# OttoPi06a-RPi3AHAT.net
KiCad netlist of a schematic drawn in EAGLE
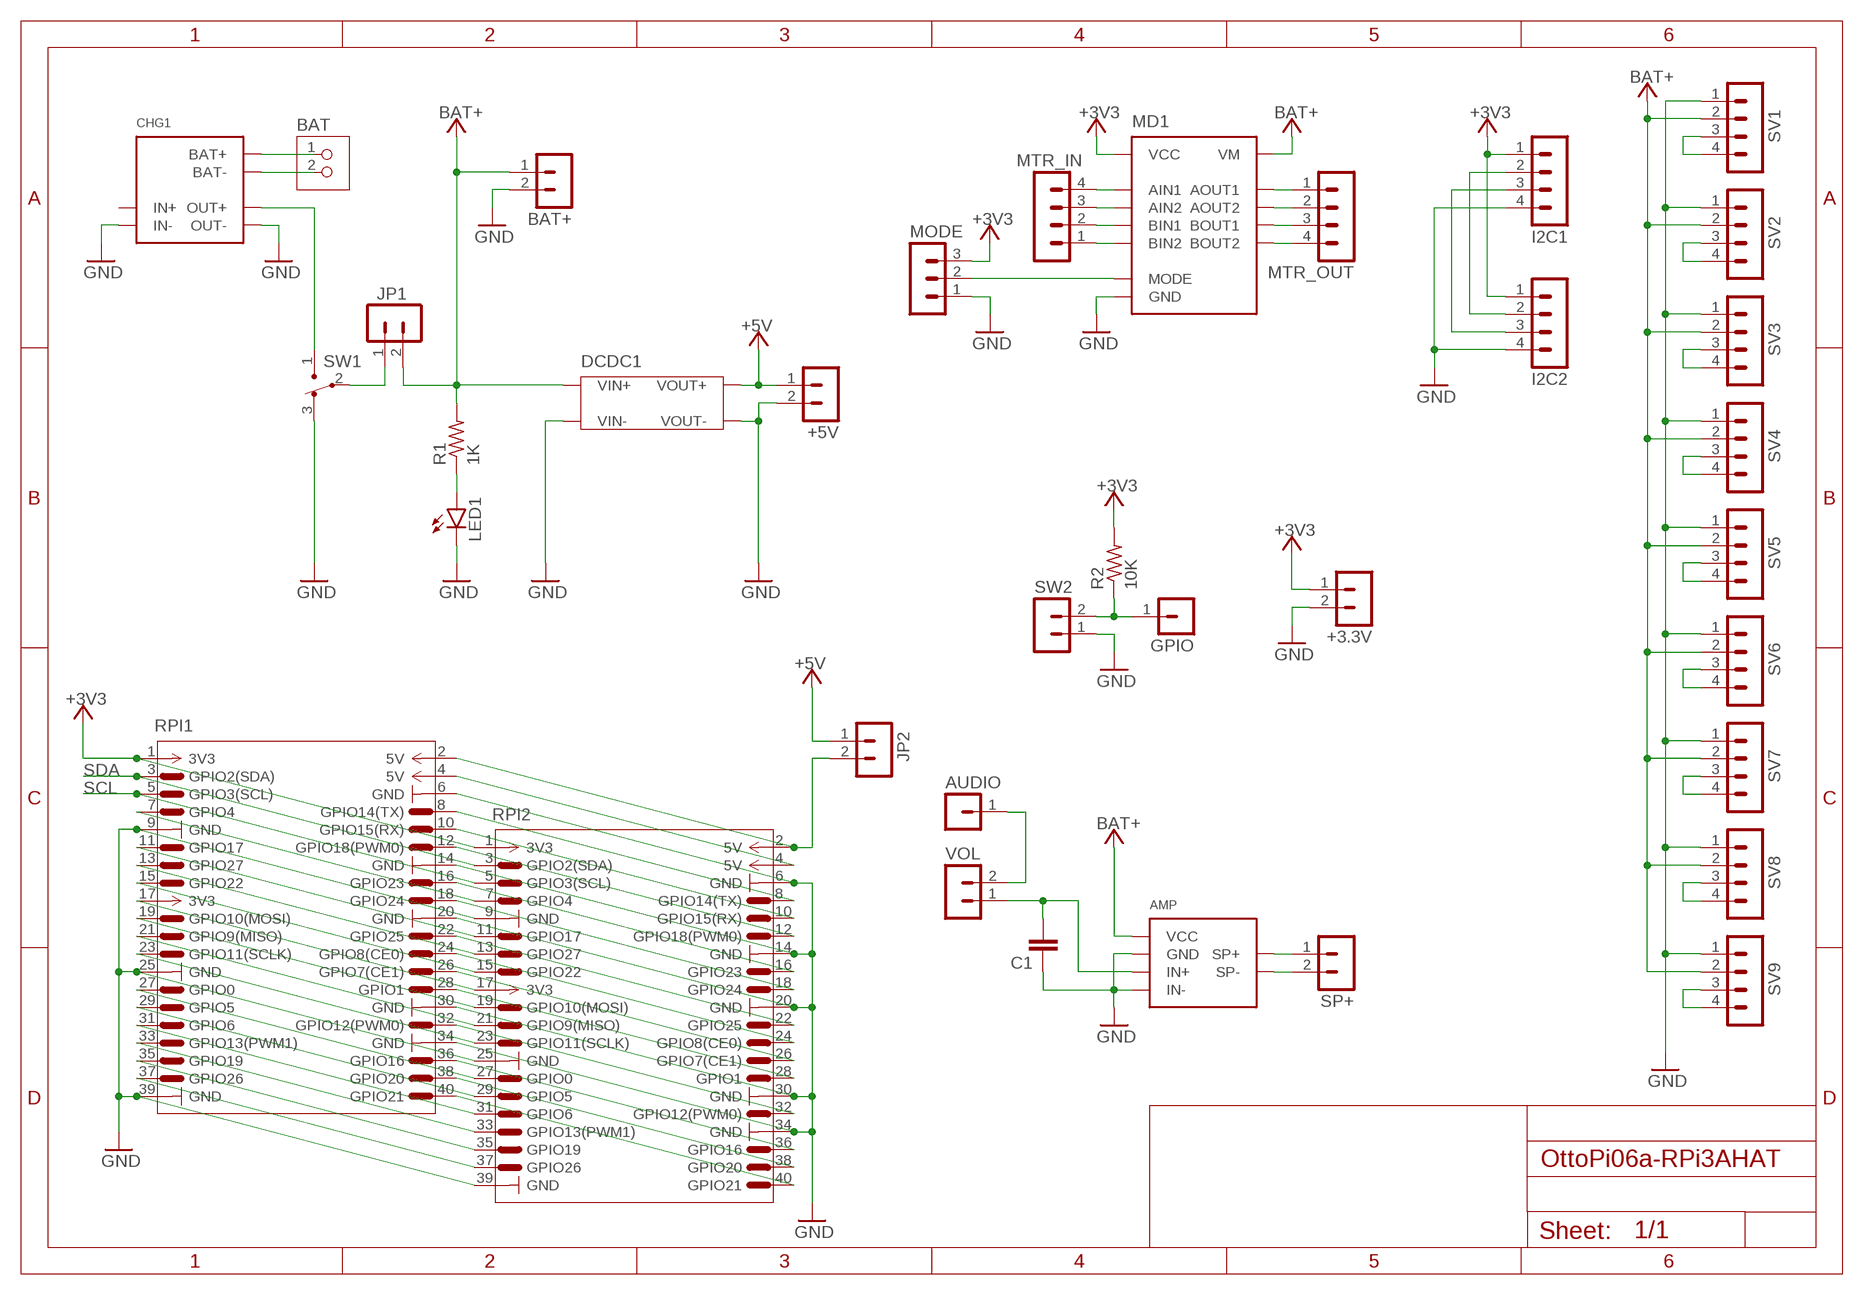
[diagram p0: schematic, sheet 1]

(export (version "E")
  (design (tool "Eeschema 10.0.6"))
  (components
    (comp (ref "+3.3V")
      (value "PINHEAD-MA02-1")
      (footprint "eagle-import:PINHEAD-MA02-1")
      (libsource (lib "eagle-import") (part "PINHEAD-MA02-1"))
    )
    (comp (ref "+5V")
      (value "PINHEAD-MA02-1")
      (footprint "eagle-import:PINHEAD-MA02-1")
      (libsource (lib "eagle-import") (part "PINHEAD-MA02-1"))
    )
    (comp (ref "AMP")
      (value "PAM8012MOD")
      (footprint "eagle-import:PAM8012MOD-A")
      (libsource (lib "eagle-import") (part "PAM8012MOD"))
    )
    (comp (ref "AUDIO")
      (value "PINHEAD-MA01-1")
      (footprint "eagle-import:PINHEAD-MA01-1")
      (libsource (lib "eagle-import") (part "PINHEAD-MA01-1"))
    )
    (comp (ref "BAT")
      (value "JST-PH2")
      (footprint "eagle-import:JST-PH2")
      (libsource (lib "eagle-import") (part "JST-PH2"))
    )
    (comp (ref "BAT+")
      (value "PINHEAD-MA02-1")
      (footprint "eagle-import:PINHEAD-MA02-1")
      (libsource (lib "eagle-import") (part "PINHEAD-MA02-1"))
    )
    (comp (ref "C1")
      (value "C-EU025-024X044")
      (footprint "eagle-import:C025-024X044")
      (libsource (lib "eagle-import") (part "C-EU025-024X044"))
    )
    (comp (ref "CHG1")
      (value "TP4056MOD1")
      (footprint "eagle-import:TP4056MOD1")
      (libsource (lib "eagle-import") (part "TP4056MOD1"))
    )
    (comp (ref "DCDC1")
      (value "DCDC-MT3608-MODUSB")
      (footprint "eagle-import:DCDC-MT3608-MOD2-USB")
      (libsource (lib "eagle-import") (part "DCDC-MT3608-MODUSB"))
    )
    (comp (ref "GPIO")
      (value "PINHEAD-MA01-1")
      (footprint "eagle-import:PINHEAD-MA01-1")
      (libsource (lib "eagle-import") (part "PINHEAD-MA01-1"))
    )
    (comp (ref "I2C1")
      (value "PINHEAD-MA04-1")
      (footprint "eagle-import:PINHEAD-MA04-1")
      (libsource (lib "eagle-import") (part "PINHEAD-MA04-1"))
    )
    (comp (ref "I2C2")
      (value "PINHEAD-MA04-1")
      (footprint "eagle-import:PINHEAD-MA04-1")
      (libsource (lib "eagle-import") (part "PINHEAD-MA04-1"))
    )
    (comp (ref "JP1")
      (value "PINHEAD-MA02-1")
      (footprint "eagle-import:PINHEAD-MA02-1")
      (libsource (lib "eagle-import") (part "PINHEAD-MA02-1"))
    )
    (comp (ref "JP2")
      (value "PINHEAD-MA02-1")
      (footprint "eagle-import:PINHEAD-MA02-1")
      (libsource (lib "eagle-import") (part "PINHEAD-MA02-1"))
    )
    (comp (ref "LED1")
      (value "LED3MM")
      (footprint "eagle-import:LED3MM")
      (libsource (lib "eagle-import") (part "LED3MM"))
    )
    (comp (ref "MD1")
      (value "DRV8835MOD")
      (footprint "eagle-import:DRV8835MOD")
      (libsource (lib "eagle-import") (part "DRV8835MOD"))
    )
    (comp (ref "MODE")
      (value "PINHEAD-MA03-1")
      (footprint "eagle-import:PINHEAD-MA03-1")
      (libsource (lib "eagle-import") (part "PINHEAD-MA03-1"))
    )
    (comp (ref "MTR_IN")
      (value "PINHEAD-MA04-1")
      (footprint "eagle-import:PINHEAD-MA04-1")
      (libsource (lib "eagle-import") (part "PINHEAD-MA04-1"))
    )
    (comp (ref "MTR_OUT")
      (value "PINHEAD-MA04-1")
      (footprint "eagle-import:PINHEAD-MA04-1")
      (libsource (lib "eagle-import") (part "PINHEAD-MA04-1"))
    )
    (comp (ref "R1")
      (value "1K")
      (footprint "eagle-import:0204_7")
      (libsource (lib "eagle-import") (part "R-US_0204/7"))
    )
    (comp (ref "R2")
      (value "10K")
      (footprint "eagle-import:0204_7")
      (libsource (lib "eagle-import") (part "R-US_0204/7"))
    )
    (comp (ref "RPI1")
      (value "RPI-PIN")
      (footprint "eagle-import:RPI-PIN")
      (libsource (lib "eagle-import") (part "RPI-PIN"))
    )
    (comp (ref "RPI2")
      (value "RPI-PIN")
      (footprint "eagle-import:RPI-PIN")
      (libsource (lib "eagle-import") (part "RPI-PIN"))
    )
    (comp (ref "SP+")
      (value "PINHEAD-MA02-1")
      (footprint "eagle-import:PINHEAD-MA02-1")
      (libsource (lib "eagle-import") (part "PINHEAD-MA02-1"))
    )
    (comp (ref "SV1")
      (value "PINHEAD-MA04-1")
      (footprint "eagle-import:PINHEAD-MA04-1")
      (libsource (lib "eagle-import") (part "PINHEAD-MA04-1"))
    )
    (comp (ref "SV2")
      (value "PINHEAD-MA04-1")
      (footprint "eagle-import:PINHEAD-MA04-1")
      (libsource (lib "eagle-import") (part "PINHEAD-MA04-1"))
    )
    (comp (ref "SV3")
      (value "PINHEAD-MA04-1")
      (footprint "eagle-import:PINHEAD-MA04-1")
      (libsource (lib "eagle-import") (part "PINHEAD-MA04-1"))
    )
    (comp (ref "SV4")
      (value "PINHEAD-MA04-1")
      (footprint "eagle-import:PINHEAD-MA04-1")
      (libsource (lib "eagle-import") (part "PINHEAD-MA04-1"))
    )
    (comp (ref "SV5")
      (value "PINHEAD-MA04-1")
      (footprint "eagle-import:PINHEAD-MA04-1")
      (libsource (lib "eagle-import") (part "PINHEAD-MA04-1"))
    )
    (comp (ref "SV6")
      (value "PINHEAD-MA04-1")
      (footprint "eagle-import:PINHEAD-MA04-1")
      (libsource (lib "eagle-import") (part "PINHEAD-MA04-1"))
    )
    (comp (ref "SV7")
      (value "PINHEAD-MA04-1")
      (footprint "eagle-import:PINHEAD-MA04-1")
      (libsource (lib "eagle-import") (part "PINHEAD-MA04-1"))
    )
    (comp (ref "SV8")
      (value "PINHEAD-MA04-1")
      (footprint "eagle-import:PINHEAD-MA04-1")
      (libsource (lib "eagle-import") (part "PINHEAD-MA04-1"))
    )
    (comp (ref "SV9")
      (value "PINHEAD-MA04-1")
      (footprint "eagle-import:PINHEAD-MA04-1")
      (libsource (lib "eagle-import") (part "PINHEAD-MA04-1"))
    )
    (comp (ref "SW1")
      (value "SW3-1")
      (footprint "eagle-import:SW3-1")
      (fields (field (name "MF") "HiLetgo"))
      (libsource (lib "eagle-import") (part "SW3-1"))
    )
    (comp (ref "SW2")
      (value "PINHEAD-MA02-1")
      (footprint "eagle-import:PINHEAD-MA02-1")
      (libsource (lib "eagle-import") (part "PINHEAD-MA02-1"))
    )
    (comp (ref "VOL")
      (value "PINHEAD-MA02-1")
      (footprint "eagle-import:PINHEAD-MA02-1")
      (libsource (lib "eagle-import") (part "PINHEAD-MA02-1"))
    )
  )
  (nets
    (net (code "1") (name "+3V3") (class "Default")
      (node (ref "+3.3V") (pin "1") (pinfunction "1_1") (pintype "passive"))
      (node (ref "I2C1") (pin "1") (pinfunction "1_1") (pintype "passive"))
      (node (ref "I2C2") (pin "1") (pinfunction "1_1") (pintype "passive"))
      (node (ref "MD1") (pin "VCC") (pinfunction "VCC_VCC") (pintype "input"))
      (node (ref "MODE") (pin "3") (pinfunction "3_3") (pintype "passive"))
      (node (ref "R2") (pin "2") (pinfunction "2_2") (pintype "passive"))
      (node (ref "RPI1") (pin "1") (pinfunction "3V3_1") (pintype "passive"))
      (node (ref "RPI2") (pin "1") (pinfunction "3V3_1") (pintype "passive"))
    )
    (net (code "2") (name "+5V") (class "Default")
      (node (ref "+5V") (pin "1") (pinfunction "1_1") (pintype "passive"))
      (node (ref "DCDC1") (pin "VOUT+") (pinfunction "VOUT+_VOUT+") (pintype "power_in"))
      (node (ref "JP2") (pin "1") (pinfunction "1_1") (pintype "passive"))
    )
    (net (code "3") (name "/SCL") (class "Default")
      (node (ref "I2C1") (pin "3") (pinfunction "3_3") (pintype "passive"))
      (node (ref "I2C2") (pin "3") (pinfunction "3_3") (pintype "passive"))
      (node (ref "RPI1") (pin "5") (pinfunction "GPIO3(SCL)_5") (pintype "passive"))
      (node (ref "RPI2") (pin "5") (pinfunction "GPIO3(SCL)_5") (pintype "passive"))
    )
    (net (code "4") (name "/SDA") (class "Default")
      (node (ref "I2C1") (pin "2") (pinfunction "2_2") (pintype "passive"))
      (node (ref "I2C2") (pin "2") (pinfunction "2_2") (pintype "passive"))
      (node (ref "RPI1") (pin "3") (pinfunction "GPIO2(SDA)_3") (pintype "passive"))
      (node (ref "RPI2") (pin "3") (pinfunction "GPIO2(SDA)_3") (pintype "passive"))
    )
    (net (code "5") (name "BAT+") (class "Default")
      (node (ref "AMP") (pin "V+") (pinfunction "VCC_V+") (pintype "passive"))
      (node (ref "BAT+") (pin "1") (pinfunction "1_1") (pintype "passive"))
      (node (ref "DCDC1") (pin "VIN+") (pinfunction "VIN+_VIN+") (pintype "power_in"))
      (node (ref "JP1") (pin "2") (pinfunction "2_2") (pintype "passive"))
      (node (ref "MD1") (pin "VM") (pinfunction "VM_VM") (pintype "input"))
      (node (ref "R1") (pin "2") (pinfunction "2_2") (pintype "passive"))
      (node (ref "SV1") (pin "2") (pinfunction "2_2") (pintype "passive"))
      (node (ref "SV2") (pin "2") (pinfunction "2_2") (pintype "passive"))
      (node (ref "SV3") (pin "2") (pinfunction "2_2") (pintype "passive"))
      (node (ref "SV4") (pin "2") (pinfunction "2_2") (pintype "passive"))
      (node (ref "SV5") (pin "2") (pinfunction "2_2") (pintype "passive"))
      (node (ref "SV6") (pin "2") (pinfunction "2_2") (pintype "passive"))
      (node (ref "SV7") (pin "2") (pinfunction "2_2") (pintype "passive"))
      (node (ref "SV8") (pin "2") (pinfunction "2_2") (pintype "passive"))
      (node (ref "SV9") (pin "2") (pinfunction "2_2") (pintype "passive"))
    )
    (net (code "6") (name "GND") (class "Default")
      (node (ref "+3.3V") (pin "2") (pinfunction "2_2") (pintype "passive"))
      (node (ref "+5V") (pin "2") (pinfunction "2_2") (pintype "passive"))
      (node (ref "AMP") (pin "GND") (pinfunction "GND_GND") (pintype "passive"))
      (node (ref "AMP") (pin "IN-") (pinfunction "IN-_IN-") (pintype "input"))
      (node (ref "BAT+") (pin "2") (pinfunction "2_2") (pintype "passive"))
      (node (ref "C1") (pin "1") (pinfunction "1_1") (pintype "passive"))
      (node (ref "CHG1") (pin "IN-") (pinfunction "IN-_IN-") (pintype "passive"))
      (node (ref "CHG1") (pin "OUT-") (pinfunction "OUT-_OUT-") (pintype "passive"))
      (node (ref "DCDC1") (pin "VIN-") (pinfunction "VIN-_VIN-") (pintype "power_in"))
      (node (ref "DCDC1") (pin "VOUT-") (pinfunction "VOUT-_VOUT-") (pintype "power_in"))
      (node (ref "I2C1") (pin "4") (pinfunction "4_4") (pintype "passive"))
      (node (ref "I2C2") (pin "4") (pinfunction "4_4") (pintype "passive"))
      (node (ref "LED1") (pin "K") (pinfunction "C_K") (pintype "passive"))
      (node (ref "MD1") (pin "GND") (pinfunction "GND_GND") (pintype "power_in"))
      (node (ref "MODE") (pin "1") (pinfunction "1_1") (pintype "passive"))
      (node (ref "RPI1") (pin "14") (pinfunction "GND_14") (pintype "passive"))
      (node (ref "RPI1") (pin "20") (pinfunction "GND_20") (pintype "passive"))
      (node (ref "RPI1") (pin "25") (pinfunction "GND_25") (pintype "passive"))
      (node (ref "RPI1") (pin "30") (pinfunction "GND_30") (pintype "passive"))
      (node (ref "RPI1") (pin "34") (pinfunction "GND_34") (pintype "passive"))
      (node (ref "RPI1") (pin "39") (pinfunction "GND_39") (pintype "passive"))
      (node (ref "RPI1") (pin "6") (pinfunction "GND_6") (pintype "passive"))
      (node (ref "RPI1") (pin "9") (pinfunction "GND_9") (pintype "passive"))
      (node (ref "RPI2") (pin "14") (pinfunction "GND_14") (pintype "passive"))
      (node (ref "RPI2") (pin "20") (pinfunction "GND_20") (pintype "passive"))
      (node (ref "RPI2") (pin "25") (pinfunction "GND_25") (pintype "passive"))
      (node (ref "RPI2") (pin "30") (pinfunction "GND_30") (pintype "passive"))
      (node (ref "RPI2") (pin "34") (pinfunction "GND_34") (pintype "passive"))
      (node (ref "RPI2") (pin "39") (pinfunction "GND_39") (pintype "passive"))
      (node (ref "RPI2") (pin "6") (pinfunction "GND_6") (pintype "passive"))
      (node (ref "RPI2") (pin "9") (pinfunction "GND_9") (pintype "passive"))
      (node (ref "SV1") (pin "1") (pinfunction "1_1") (pintype "passive"))
      (node (ref "SV2") (pin "1") (pinfunction "1_1") (pintype "passive"))
      (node (ref "SV3") (pin "1") (pinfunction "1_1") (pintype "passive"))
      (node (ref "SV4") (pin "1") (pinfunction "1_1") (pintype "passive"))
      (node (ref "SV5") (pin "1") (pinfunction "1_1") (pintype "passive"))
      (node (ref "SV6") (pin "1") (pinfunction "1_1") (pintype "passive"))
      (node (ref "SV7") (pin "1") (pinfunction "1_1") (pintype "passive"))
      (node (ref "SV8") (pin "1") (pinfunction "1_1") (pintype "passive"))
      (node (ref "SV9") (pin "1") (pinfunction "1_1") (pintype "passive"))
      (node (ref "SW1") (pin "3") (pinfunction "3_3") (pintype "passive"))
      (node (ref "SW2") (pin "1") (pinfunction "1_1") (pintype "passive"))
    )
    (net (code "7") (name "Net-(AMP-PadIN+)") (class "Default")
      (node (ref "AMP") (pin "IN+") (pinfunction "IN+_IN+") (pintype "input"))
      (node (ref "C1") (pin "2") (pinfunction "2_2") (pintype "passive"))
      (node (ref "VOL") (pin "1") (pinfunction "1_1") (pintype "passive"))
    )
    (net (code "8") (name "Net-(AMP-SP+)") (class "Default")
      (node (ref "AMP") (pin "SP+@1") (pinfunction "SP+_SP+@1") (pintype "output"))
      (node (ref "SP+") (pin "1") (pinfunction "1_1") (pintype "passive"))
    )
    (net (code "9") (name "Net-(AMP-SP-)") (class "Default")
      (node (ref "AMP") (pin "SP-@1") (pinfunction "SP-_SP-@1") (pintype "output"))
      (node (ref "SP+") (pin "2") (pinfunction "2_2") (pintype "passive"))
    )
    (net (code "10") (name "Net-(AUDIO-Pad1)") (class "Default")
      (node (ref "AUDIO") (pin "1") (pinfunction "1_1") (pintype "passive"))
      (node (ref "VOL") (pin "2") (pinfunction "2_2") (pintype "passive"))
    )
    (net (code "11") (name "Net-(BAT-Pad1)") (class "Default")
      (node (ref "BAT") (pin "1") (pinfunction "1_1") (pintype "passive"))
      (node (ref "CHG1") (pin "BAT+") (pinfunction "BAT+_BAT+") (pintype "passive"))
    )
    (net (code "12") (name "Net-(BAT-Pad2)") (class "Default")
      (node (ref "BAT") (pin "2") (pinfunction "2_2") (pintype "passive"))
      (node (ref "CHG1") (pin "BAT-") (pinfunction "BAT-_BAT-") (pintype "passive"))
    )
    (net (code "13") (name "Net-(CHG1-PadOUT+)") (class "Default")
      (node (ref "CHG1") (pin "OUT+") (pinfunction "OUT+_OUT+") (pintype "passive"))
      (node (ref "SW1") (pin "1") (pinfunction "1_1") (pintype "passive"))
    )
    (net (code "14") (name "Net-(GPIO-Pad1)") (class "Default")
      (node (ref "GPIO") (pin "1") (pinfunction "1_1") (pintype "passive"))
      (node (ref "R2") (pin "1") (pinfunction "1_1") (pintype "passive"))
      (node (ref "SW2") (pin "2") (pinfunction "2_2") (pintype "passive"))
    )
    (net (code "15") (name "Net-(JP1-Pad1)") (class "Default")
      (node (ref "JP1") (pin "1") (pinfunction "1_1") (pintype "passive"))
      (node (ref "SW1") (pin "2") (pinfunction "2_2") (pintype "passive"))
    )
    (net (code "16") (name "Net-(JP2-Pad2)") (class "Default")
      (node (ref "JP2") (pin "2") (pinfunction "2_2") (pintype "passive"))
      (node (ref "RPI1") (pin "2") (pinfunction "5V_2") (pintype "passive"))
      (node (ref "RPI2") (pin "2") (pinfunction "5V_2") (pintype "passive"))
    )
    (net (code "17") (name "Net-(LED1-PadA)") (class "Default")
      (node (ref "LED1") (pin "A") (pinfunction "A_A") (pintype "passive"))
      (node (ref "R1") (pin "1") (pinfunction "1_1") (pintype "passive"))
    )
    (net (code "18") (name "Net-(MD1-PadAIN1)") (class "Default")
      (node (ref "MD1") (pin "AIN1") (pinfunction "AIN1_AIN1") (pintype "input"))
      (node (ref "MTR_IN") (pin "4") (pinfunction "4_4") (pintype "passive"))
    )
    (net (code "19") (name "Net-(MD1-PadAIN2)") (class "Default")
      (node (ref "MD1") (pin "AIN2") (pinfunction "AIN2_AIN2") (pintype "input"))
      (node (ref "MTR_IN") (pin "3") (pinfunction "3_3") (pintype "passive"))
    )
    (net (code "20") (name "Net-(MD1-PadAOUT1)") (class "Default")
      (node (ref "MD1") (pin "AOUT1") (pinfunction "AOUT1_AOUT1") (pintype "output"))
      (node (ref "MTR_OUT") (pin "1") (pinfunction "1_1") (pintype "passive"))
    )
    (net (code "21") (name "Net-(MD1-PadAOUT2)") (class "Default")
      (node (ref "MD1") (pin "AOUT2") (pinfunction "AOUT2_AOUT2") (pintype "output"))
      (node (ref "MTR_OUT") (pin "2") (pinfunction "2_2") (pintype "passive"))
    )
    (net (code "22") (name "Net-(MD1-PadBIN1)") (class "Default")
      (node (ref "MD1") (pin "BIN1") (pinfunction "BIN1_BIN1") (pintype "input"))
      (node (ref "MTR_IN") (pin "2") (pinfunction "2_2") (pintype "passive"))
    )
    (net (code "23") (name "Net-(MD1-PadBIN2)") (class "Default")
      (node (ref "MD1") (pin "BIN2") (pinfunction "BIN2_BIN2") (pintype "input"))
      (node (ref "MTR_IN") (pin "1") (pinfunction "1_1") (pintype "passive"))
    )
    (net (code "24") (name "Net-(MD1-PadBOUT1)") (class "Default")
      (node (ref "MD1") (pin "BOUT1") (pinfunction "BOUT1_BOUT1") (pintype "output"))
      (node (ref "MTR_OUT") (pin "3") (pinfunction "3_3") (pintype "passive"))
    )
    (net (code "25") (name "Net-(MD1-PadBOUT2)") (class "Default")
      (node (ref "MD1") (pin "BOUT2") (pinfunction "BOUT2_BOUT2") (pintype "output"))
      (node (ref "MTR_OUT") (pin "4") (pinfunction "4_4") (pintype "passive"))
    )
    (net (code "26") (name "Net-(MD1-PadMODE)") (class "Default")
      (node (ref "MD1") (pin "MODE") (pinfunction "MODE_MODE") (pintype "input"))
      (node (ref "MODE") (pin "2") (pinfunction "2_2") (pintype "passive"))
    )
    (net (code "27") (name "Net-(RPI1-3V3-Pad17)") (class "Default")
      (node (ref "RPI1") (pin "17") (pinfunction "3V3_17") (pintype "passive"))
      (node (ref "RPI2") (pin "17") (pinfunction "3V3_17") (pintype "passive"))
    )
    (net (code "28") (name "Net-(RPI1-5V-Pad4)") (class "Default")
      (node (ref "RPI1") (pin "4") (pinfunction "5V_4") (pintype "passive"))
      (node (ref "RPI2") (pin "4") (pinfunction "5V_4") (pintype "passive"))
    )
    (net (code "29") (name "Net-(RPI1-GPIO0)") (class "Default")
      (node (ref "RPI1") (pin "27") (pinfunction "GPIO0_27") (pintype "passive"))
      (node (ref "RPI2") (pin "27") (pinfunction "GPIO0_27") (pintype "passive"))
    )
    (net (code "30") (name "Net-(RPI1-GPIO1)") (class "Default")
      (node (ref "RPI1") (pin "28") (pinfunction "GPIO1_28") (pintype "passive"))
      (node (ref "RPI2") (pin "28") (pinfunction "GPIO1_28") (pintype "passive"))
    )
    (net (code "31") (name "Net-(RPI1-GPIO4)") (class "Default")
      (node (ref "RPI1") (pin "7") (pinfunction "GPIO4_7") (pintype "passive"))
      (node (ref "RPI2") (pin "7") (pinfunction "GPIO4_7") (pintype "passive"))
    )
    (net (code "32") (name "Net-(RPI1-GPIO5)") (class "Default")
      (node (ref "RPI1") (pin "29") (pinfunction "GPIO5_29") (pintype "passive"))
      (node (ref "RPI2") (pin "29") (pinfunction "GPIO5_29") (pintype "passive"))
    )
    (net (code "33") (name "Net-(RPI1-GPIO6)") (class "Default")
      (node (ref "RPI1") (pin "31") (pinfunction "GPIO6_31") (pintype "passive"))
      (node (ref "RPI2") (pin "31") (pinfunction "GPIO6_31") (pintype "passive"))
    )
    (net (code "34") (name "Net-(RPI1-GPIO7(CE1))") (class "Default")
      (node (ref "RPI1") (pin "26") (pinfunction "GPIO7(CE1)_26") (pintype "passive"))
      (node (ref "RPI2") (pin "26") (pinfunction "GPIO7(CE1)_26") (pintype "passive"))
    )
    (net (code "35") (name "Net-(RPI1-GPIO8(CE0))") (class "Default")
      (node (ref "RPI1") (pin "24") (pinfunction "GPIO8(CE0)_24") (pintype "passive"))
      (node (ref "RPI2") (pin "24") (pinfunction "GPIO8(CE0)_24") (pintype "passive"))
    )
    (net (code "36") (name "Net-(RPI1-GPIO9(MISO))") (class "Default")
      (node (ref "RPI1") (pin "21") (pinfunction "GPIO9(MISO)_21") (pintype "passive"))
      (node (ref "RPI2") (pin "21") (pinfunction "GPIO9(MISO)_21") (pintype "passive"))
    )
    (net (code "37") (name "Net-(RPI1-GPIO10(MOSI))") (class "Default")
      (node (ref "RPI1") (pin "19") (pinfunction "GPIO10(MOSI)_19") (pintype "passive"))
      (node (ref "RPI2") (pin "19") (pinfunction "GPIO10(MOSI)_19") (pintype "passive"))
    )
    (net (code "38") (name "Net-(RPI1-GPIO11(SCLK))") (class "Default")
      (node (ref "RPI1") (pin "23") (pinfunction "GPIO11(SCLK)_23") (pintype "passive"))
      (node (ref "RPI2") (pin "23") (pinfunction "GPIO11(SCLK)_23") (pintype "passive"))
    )
    (net (code "39") (name "Net-(RPI1-GPIO12(PWM0))") (class "Default")
      (node (ref "RPI1") (pin "32") (pinfunction "GPIO12(PWM0)_32") (pintype "passive"))
      (node (ref "RPI2") (pin "32") (pinfunction "GPIO12(PWM0)_32") (pintype "passive"))
    )
    (net (code "40") (name "Net-(RPI1-GPIO13(PWM1))") (class "Default")
      (node (ref "RPI1") (pin "33") (pinfunction "GPIO13(PWM1)_33") (pintype "passive"))
      (node (ref "RPI2") (pin "33") (pinfunction "GPIO13(PWM1)_33") (pintype "passive"))
    )
    (net (code "41") (name "Net-(RPI1-GPIO14(TX))") (class "Default")
      (node (ref "RPI1") (pin "8") (pinfunction "GPIO14(TX)_8") (pintype "passive"))
      (node (ref "RPI2") (pin "8") (pinfunction "GPIO14(TX)_8") (pintype "passive"))
    )
    (net (code "42") (name "Net-(RPI1-GPIO15(RX))") (class "Default")
      (node (ref "RPI1") (pin "10") (pinfunction "GPIO15(RX)_10") (pintype "passive"))
      (node (ref "RPI2") (pin "10") (pinfunction "GPIO15(RX)_10") (pintype "passive"))
    )
    (net (code "43") (name "Net-(RPI1-GPIO16)") (class "Default")
      (node (ref "RPI1") (pin "36") (pinfunction "GPIO16_36") (pintype "passive"))
      (node (ref "RPI2") (pin "36") (pinfunction "GPIO16_36") (pintype "passive"))
    )
    (net (code "44") (name "Net-(RPI1-GPIO17)") (class "Default")
      (node (ref "RPI1") (pin "11") (pinfunction "GPIO17_11") (pintype "passive"))
      (node (ref "RPI2") (pin "11") (pinfunction "GPIO17_11") (pintype "passive"))
    )
    (net (code "45") (name "Net-(RPI1-GPIO18(PWM0))") (class "Default")
      (node (ref "RPI1") (pin "12") (pinfunction "GPIO18(PWM0)_12") (pintype "passive"))
      (node (ref "RPI2") (pin "12") (pinfunction "GPIO18(PWM0)_12") (pintype "passive"))
    )
    (net (code "46") (name "Net-(RPI1-GPIO19)") (class "Default")
      (node (ref "RPI1") (pin "35") (pinfunction "GPIO19_35") (pintype "passive"))
      (node (ref "RPI2") (pin "35") (pinfunction "GPIO19_35") (pintype "passive"))
    )
    (net (code "47") (name "Net-(RPI1-GPIO20)") (class "Default")
      (node (ref "RPI1") (pin "38") (pinfunction "GPIO20_38") (pintype "passive"))
      (node (ref "RPI2") (pin "38") (pinfunction "GPIO20_38") (pintype "passive"))
    )
    (net (code "48") (name "Net-(RPI1-GPIO21)") (class "Default")
      (node (ref "RPI1") (pin "40") (pinfunction "GPIO21_40") (pintype "passive"))
      (node (ref "RPI2") (pin "40") (pinfunction "GPIO21_40") (pintype "passive"))
    )
    (net (code "49") (name "Net-(RPI1-GPIO22)") (class "Default")
      (node (ref "RPI1") (pin "15") (pinfunction "GPIO22_15") (pintype "passive"))
      (node (ref "RPI2") (pin "15") (pinfunction "GPIO22_15") (pintype "passive"))
    )
    (net (code "50") (name "Net-(RPI1-GPIO23)") (class "Default")
      (node (ref "RPI1") (pin "16") (pinfunction "GPIO23_16") (pintype "passive"))
      (node (ref "RPI2") (pin "16") (pinfunction "GPIO23_16") (pintype "passive"))
    )
    (net (code "51") (name "Net-(RPI1-GPIO24)") (class "Default")
      (node (ref "RPI1") (pin "18") (pinfunction "GPIO24_18") (pintype "passive"))
      (node (ref "RPI2") (pin "18") (pinfunction "GPIO24_18") (pintype "passive"))
    )
    (net (code "52") (name "Net-(RPI1-GPIO25)") (class "Default")
      (node (ref "RPI1") (pin "22") (pinfunction "GPIO25_22") (pintype "passive"))
      (node (ref "RPI2") (pin "22") (pinfunction "GPIO25_22") (pintype "passive"))
    )
    (net (code "53") (name "Net-(RPI1-GPIO26)") (class "Default")
      (node (ref "RPI1") (pin "37") (pinfunction "GPIO26_37") (pintype "passive"))
      (node (ref "RPI2") (pin "37") (pinfunction "GPIO26_37") (pintype "passive"))
    )
    (net (code "54") (name "Net-(RPI1-GPIO27)") (class "Default")
      (node (ref "RPI1") (pin "13") (pinfunction "GPIO27_13") (pintype "passive"))
      (node (ref "RPI2") (pin "13") (pinfunction "GPIO27_13") (pintype "passive"))
    )
    (net (code "55") (name "Net-(SV1-Pad3)") (class "Default")
      (node (ref "SV1") (pin "3") (pinfunction "3_3") (pintype "passive"))
      (node (ref "SV1") (pin "4") (pinfunction "4_4") (pintype "passive"))
    )
    (net (code "56") (name "Net-(SV2-Pad3)") (class "Default")
      (node (ref "SV2") (pin "3") (pinfunction "3_3") (pintype "passive"))
      (node (ref "SV2") (pin "4") (pinfunction "4_4") (pintype "passive"))
    )
    (net (code "57") (name "Net-(SV3-Pad3)") (class "Default")
      (node (ref "SV3") (pin "3") (pinfunction "3_3") (pintype "passive"))
      (node (ref "SV3") (pin "4") (pinfunction "4_4") (pintype "passive"))
    )
    (net (code "58") (name "Net-(SV4-Pad3)") (class "Default")
      (node (ref "SV4") (pin "3") (pinfunction "3_3") (pintype "passive"))
      (node (ref "SV4") (pin "4") (pinfunction "4_4") (pintype "passive"))
    )
    (net (code "59") (name "Net-(SV5-Pad3)") (class "Default")
      (node (ref "SV5") (pin "3") (pinfunction "3_3") (pintype "passive"))
      (node (ref "SV5") (pin "4") (pinfunction "4_4") (pintype "passive"))
    )
    (net (code "60") (name "Net-(SV6-Pad3)") (class "Default")
      (node (ref "SV6") (pin "3") (pinfunction "3_3") (pintype "passive"))
      (node (ref "SV6") (pin "4") (pinfunction "4_4") (pintype "passive"))
    )
    (net (code "61") (name "Net-(SV7-Pad3)") (class "Default")
      (node (ref "SV7") (pin "3") (pinfunction "3_3") (pintype "passive"))
      (node (ref "SV7") (pin "4") (pinfunction "4_4") (pintype "passive"))
    )
    (net (code "62") (name "Net-(SV8-Pad3)") (class "Default")
      (node (ref "SV8") (pin "3") (pinfunction "3_3") (pintype "passive"))
      (node (ref "SV8") (pin "4") (pinfunction "4_4") (pintype "passive"))
    )
    (net (code "63") (name "Net-(SV9-Pad3)") (class "Default")
      (node (ref "SV9") (pin "3") (pinfunction "3_3") (pintype "passive"))
      (node (ref "SV9") (pin "4") (pinfunction "4_4") (pintype "passive"))
    )
    (net (code "64") (name "unconnected-(CHG1-PadIN+)") (class "Default")
      (node (ref "CHG1") (pin "IN+") (pinfunction "IN+_IN+") (pintype "passive"))
    )
  )
)
